# AirSenseV2_03.net
KiCad netlist of a schematic drawn in Altium Designer
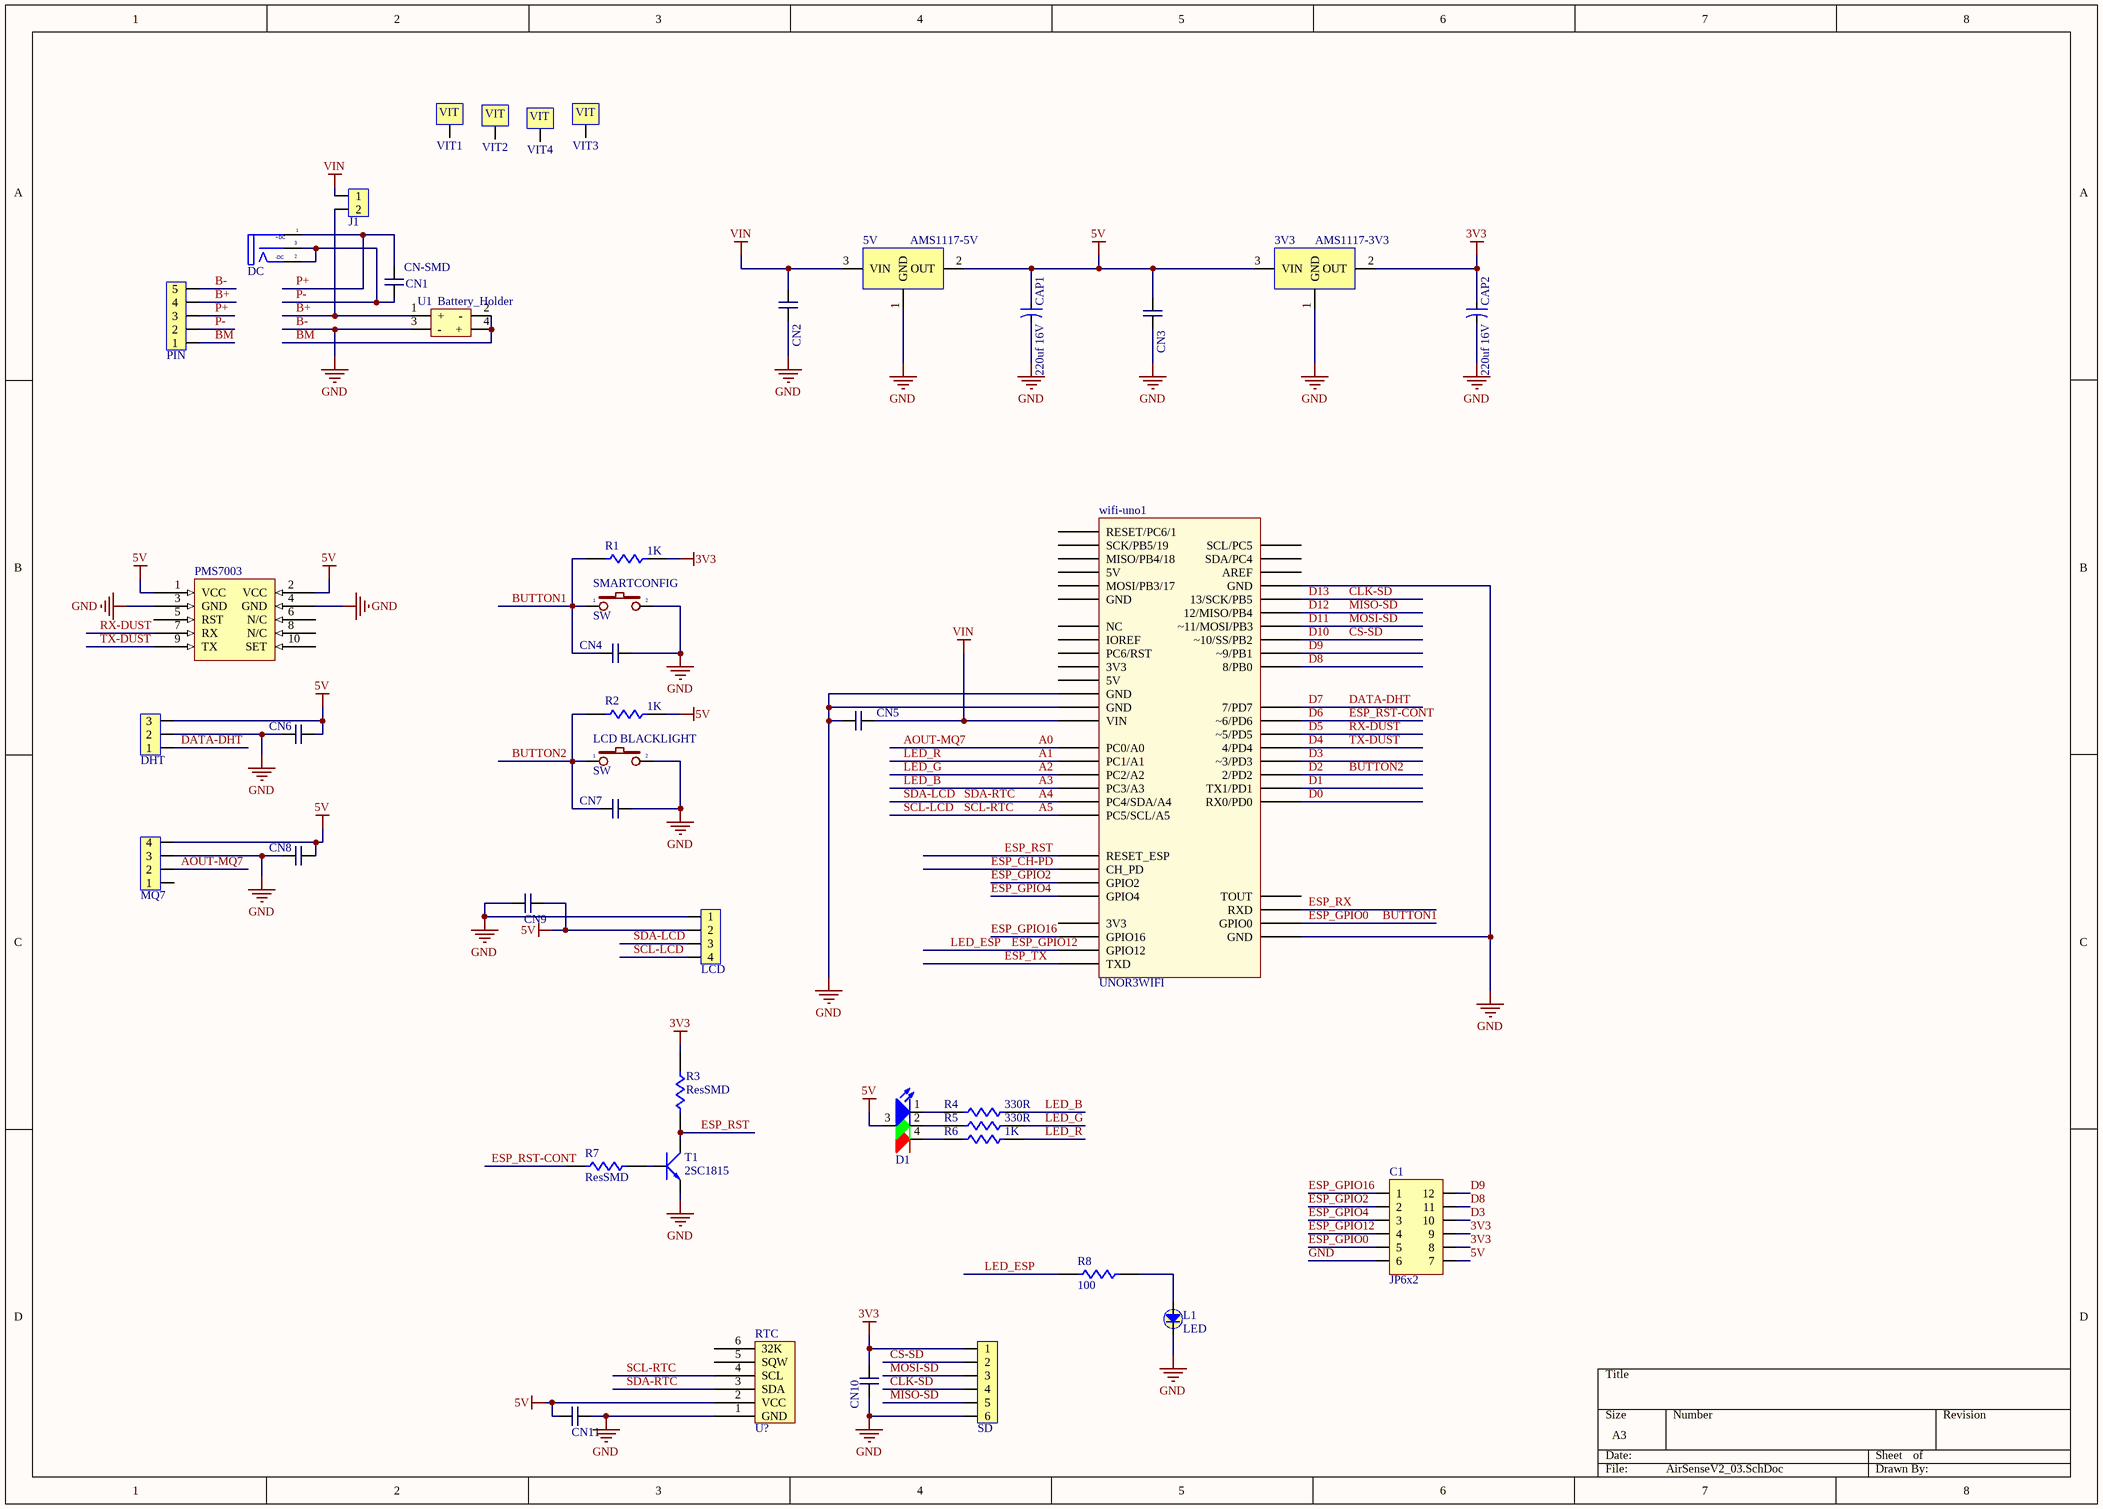
[diagram p0: AirSenseV2_03.SchDoc]

(export (version "E")
  (design (tool "Eeschema 10.0.6"))
  (components
    (comp (ref "3V3")
      (value "AMS1117-3V3")
      (footprint "SOT223")
      (description "800mA Low-Dropout Linear Regulator")
      (libsource (lib "DarkBaronLib") (part "AMS1117-3V3"))
    )
    (comp (ref "5V")
      (value "AMS1117-5V")
      (footprint "SOT223")
      (description "800mA Low-Dropout Linear Regulator")
      (libsource (lib "DarkBaronLib") (part "AMS1117-3V3"))
    )
    (comp (ref "C1")
      (value "JP6x2")
      (footprint "JP6-D2T")
      (description "WR-PHD 2.54 mm Dual Socket Header")
      (fields
        (field (name "MANUFACTURER") "Würth Elektronik eiSos GmbH")
        (field (name "PARTNO") "61301221821")
        (field (name "CREATED BY") "Karrer Zheng")
      )
      (libsource (lib "LIBRARY") (part "JP6x2"))
    )
    (comp (ref "CAP1")
      (value "220uf 16V")
      (footprint "CA-6.5x6.5")
      (description "Cap Aluminum Lytic 100uF 10V 20% (8 X 6.2mm) SMD 230mA 1000h 105C Embossed T/R")
      (libsource (lib "DarkBaronLib") (part "CAP-SMD"))
    )
    (comp (ref "CAP2")
      (value "220uf 16V")
      (footprint "CA-6.5x6.5")
      (description "Cap Aluminum Lytic 100uF 10V 20% (8 X 6.2mm) SMD 230mA 1000h 105C Embossed T/R")
      (libsource (lib "DarkBaronLib") (part "CAP-SMD"))
    )
    (comp (ref "CN1")
      (value "CN-SMD")
      (footprint "C-0805")
      (description "CAP CER 0.047UF 25V X7R 040")
      (libsource (lib "DarkBaronLib") (part "CN-SMD"))
    )
    (comp (ref "CN2")
      (value "CN-SMD")
      (footprint "C-0805")
      (description "CAP CER 0.047UF 25V X7R 040")
      (libsource (lib "DarkBaronLib") (part "CN-SMD"))
    )
    (comp (ref "CN3")
      (value "CN-SMD")
      (footprint "C-0805")
      (description "CAP CER 0.047UF 25V X7R 040")
      (libsource (lib "DarkBaronLib") (part "CN-SMD"))
    )
    (comp (ref "CN4")
      (value "CN-SMD")
      (footprint "C-0805")
      (description "CAP CER 0.047UF 25V X7R 040")
      (libsource (lib "DarkBaronLib") (part "CN-SMD"))
    )
    (comp (ref "CN5")
      (value "CN-SMD")
      (footprint "C-0805")
      (description "CAP CER 0.047UF 25V X7R 040")
      (libsource (lib "DarkBaronLib") (part "CN-SMD"))
    )
    (comp (ref "CN6")
      (value "CN-SMD")
      (footprint "C-0805")
      (description "CAP CER 0.047UF 25V X7R 040")
      (libsource (lib "DarkBaronLib") (part "CN-SMD"))
    )
    (comp (ref "CN7")
      (value "CN-SMD")
      (footprint "C-0805")
      (description "CAP CER 0.047UF 25V X7R 040")
      (libsource (lib "DarkBaronLib") (part "CN-SMD"))
    )
    (comp (ref "CN8")
      (value "CN-SMD")
      (footprint "C-0805")
      (description "CAP CER 0.047UF 25V X7R 040")
      (libsource (lib "DarkBaronLib") (part "CN-SMD"))
    )
    (comp (ref "CN9")
      (value "CN-SMD")
      (footprint "C-0805")
      (description "CAP CER 0.047UF 25V X7R 040")
      (libsource (lib "DarkBaronLib") (part "CN-SMD"))
    )
    (comp (ref "CN10")
      (value "CN-SMD")
      (footprint "C-0805")
      (description "CAP CER 0.047UF 25V X7R 040")
      (libsource (lib "DarkBaronLib") (part "CN-SMD"))
    )
    (comp (ref "CN11")
      (value "CN-SMD")
      (footprint "C-0805")
      (description "CAP CER 0.047UF 25V X7R 040")
      (libsource (lib "DarkBaronLib") (part "CN-SMD"))
    )
    (comp (ref "D1")
      (value "LED_RGB1")
      (footprint "LED RGB 5MM TYPE A")
      (libsource (lib "Tesla_Thinh") (part "LED_RGB1"))
    )
    (comp (ref "DC")
      (value "DCIN")
      (footprint "DC0")
      (description "CONN POWER JACK 2.1X5.5MM SMD")
      (libsource (lib "DarkBaronLib") (part "DCIN"))
    )
    (comp (ref "DHT")
      (value "Header3")
      (footprint "Header3")
      (description "Header IDC, 3 x 1 Pin Vertical 2.54mm Pitch (Non-Boxed, Male)")
      (libsource (lib "DarkBaronLib") (part "Header3"))
    )
    (comp (ref "J1")
      (value "JP2")
      (footprint "JP2-C1T")
      (description "WR-PHD 2.54 mm Angled Socket Header")
      (libsource (lib "DarkBaronLib") (part "JP2"))
    )
    (comp (ref "L1")
      (value "LED")
      (footprint "L-3B")
      (description "DIALIGHT         5988270107F            LED, Green, SMD, 20 mA, 2 V, 570 nm")
      (libsource (lib "DarkBaronLib") (part "LED"))
    )
    (comp (ref "LCD")
      (value "JP4")
      (footprint "JP4-C1T")
      (description "WR-PHD 2.54 mm Angled Socket Header")
      (libsource (lib "DarkBaronLib") (part "JP4"))
    )
    (comp (ref "LCD BLACKLIGHT")
      (value "SW")
      (footprint "SW1-DIP")
      (description "Switch button 2 pin")
      (libsource (lib "Tesla_Thinh") (part "SW2"))
    )
    (comp (ref "MQ7")
      (value "Header4")
      (footprint "Header4")
      (description "Header IDC, 4 x 1 Pin Vertical 2.54mm Pitch (Non-Boxed, Male)")
      (libsource (lib "DarkBaronLib") (part "Header4"))
    )
    (comp (ref "PIN")
      (value "JP5")
      (footprint "JP5-D1T")
      (description "WR-PHD 2.54 mm Angled Socket Header")
      (libsource (lib "DarkBaronLib") (part "JP5"))
    )
    (comp (ref "PMS7003")
      (value "~")
      (footprint "DUST_PMSA003")
      (libsource (lib "DarkBaronLib") (part "DUST_PMSA003"))
    )
    (comp (ref "R1")
      (value "1K")
      (footprint "R0805")
      (description "RES SMD 0.0 OHM JUMPER 1/8W 0805")
      (libsource (lib "DarkBaronLib") (part "ResSMD"))
    )
    (comp (ref "R2")
      (value "1K")
      (footprint "R0805")
      (description "RES SMD 0.0 OHM JUMPER 1/8W 0805")
      (libsource (lib "DarkBaronLib") (part "ResSMD"))
    )
    (comp (ref "R3")
      (value "ResSMD")
      (footprint "R0805")
      (description "RES SMD 0.0 OHM JUMPER 1/8W 0805")
      (libsource (lib "DarkBaronLib") (part "ResSMD"))
    )
    (comp (ref "R4")
      (value "330R")
      (footprint "R0805")
      (description "RES SMD 0.0 OHM JUMPER 1/8W 0805")
      (libsource (lib "DarkBaronLib") (part "ResSMD"))
    )
    (comp (ref "R5")
      (value "330R")
      (footprint "R0805")
      (description "RES SMD 0.0 OHM JUMPER 1/8W 0805")
      (libsource (lib "DarkBaronLib") (part "ResSMD"))
    )
    (comp (ref "R6")
      (value "1K")
      (footprint "R0805")
      (description "RES SMD 0.0 OHM JUMPER 1/8W 0805")
      (libsource (lib "DarkBaronLib") (part "ResSMD"))
    )
    (comp (ref "R7")
      (value "ResSMD")
      (footprint "R0805")
      (description "RES SMD 0.0 OHM JUMPER 1/8W 0805")
      (libsource (lib "DarkBaronLib") (part "ResSMD"))
    )
    (comp (ref "R8")
      (value "100")
      (footprint "R0805")
      (description "RES SMD 0.0 OHM JUMPER 1/8W 0805")
      (libsource (lib "DarkBaronLib") (part "ResSMD"))
    )
    (comp (ref "RTC")
      (value "U?")
      (footprint "RTC_Module")
      (libsource (lib "DarkBaronLib") (part "RTC-Module"))
    )
    (comp (ref "SD")
      (value "JP6")
      (footprint "JP6-D1T")
      (description "WR-PHD 2.54 mm Angled Socket Header")
      (libsource (lib "DarkBaronLib") (part "JP6"))
    )
    (comp (ref "SMARTCONFIG")
      (value "SW")
      (footprint "SW1-DIP")
      (description "Switch button 2 pin")
      (libsource (lib "Tesla_Thinh") (part "SW2"))
    )
    (comp (ref "T1")
      (value "2SC1815")
      (footprint "SOT23-BCE")
      (description "Bipolar Transistors - BJT NPN Epitaxial Sil")
      (libsource (lib "DarkBaronLib") (part "2SC1815"))
    )
    (comp (ref "U1")
      (value "Battery_Holder")
      (footprint "18650x2")
      (libsource (lib "DarkBaronLib") (part "Battery_Holder"))
    )
    (comp (ref "VIT1")
      (value "VIT")
      (footprint "VIT")
      (description "Oc Vit")
      (libsource (lib "DarkBaronLib") (part "VIT"))
    )
    (comp (ref "VIT2")
      (value "VIT")
      (footprint "VIT")
      (description "Oc Vit")
      (libsource (lib "DarkBaronLib") (part "VIT"))
    )
    (comp (ref "VIT3")
      (value "VIT")
      (footprint "VIT")
      (description "Oc Vit")
      (libsource (lib "DarkBaronLib") (part "VIT"))
    )
    (comp (ref "VIT4")
      (value "VIT")
      (footprint "VIT")
      (description "Oc Vit")
      (libsource (lib "DarkBaronLib") (part "VIT"))
    )
    (comp (ref "wifi-uno1")
      (value "UNOR3WIFI")
      (footprint "UNOR3WIFI")
      (libsource (lib "AirSenseV2_03") (part "UNOR3WIFI"))
    )
  )
  (nets
    (net (code "1") (name "/A0") (class "Default")
      (node (ref "MQ7") (pin "2") (pinfunction "2_2") (pintype "passive"))
      (node (ref "wifi-uno1") (pin "PC0") (pinfunction "PC0/A0_PC0") (pintype "passive"))
    )
    (net (code "2") (name "/A1") (class "Default")
      (node (ref "R6") (pin "1") (pinfunction "1_1") (pintype "passive"))
      (node (ref "wifi-uno1") (pin "PC1") (pinfunction "PC1/A1_PC1") (pintype "passive"))
    )
    (net (code "3") (name "/A2") (class "Default")
      (node (ref "R5") (pin "1") (pinfunction "1_1") (pintype "passive"))
      (node (ref "wifi-uno1") (pin "PC2") (pinfunction "PC2/A2_PC2") (pintype "passive"))
    )
    (net (code "4") (name "/A3") (class "Default")
      (node (ref "R4") (pin "1") (pinfunction "1_1") (pintype "passive"))
      (node (ref "wifi-uno1") (pin "PC3") (pinfunction "PC3/A3_PC3") (pintype "passive"))
    )
    (net (code "5") (name "/A4") (class "Default")
      (node (ref "LCD") (pin "3") (pinfunction "3_3") (pintype "passive"))
      (node (ref "RTC") (pin "3") (pinfunction "SDA_3") (pintype "passive"))
      (node (ref "wifi-uno1") (pin "PC4") (pinfunction "PC4/SDA/A4_PC4") (pintype "passive"))
    )
    (net (code "6") (name "/A5") (class "Default")
      (node (ref "LCD") (pin "4") (pinfunction "4_4") (pintype "passive"))
      (node (ref "RTC") (pin "4") (pinfunction "SCL_4") (pintype "passive"))
      (node (ref "wifi-uno1") (pin "PC5") (pinfunction "PC5/SCL/A5_PC5") (pintype "passive"))
    )
    (net (code "7") (name "/B+") (class "Default")
      (node (ref "J1") (pin "2") (pinfunction "2_2") (pintype "passive"))
      (node (ref "PIN") (pin "4") (pinfunction "4_4") (pintype "passive"))
      (node (ref "U1") (pin "1") (pinfunction "+_1") (pintype "power_in"))
    )
    (net (code "8") (name "/BM") (class "Default")
      (node (ref "PIN") (pin "1") (pinfunction "1_1") (pintype "passive"))
      (node (ref "U1") (pin "2") (pinfunction "-_2") (pintype "power_in"))
      (node (ref "U1") (pin "4") (pinfunction "+_4") (pintype "power_in"))
    )
    (net (code "9") (name "/BUTTON1") (class "Default")
      (node (ref "C1") (pin "5") (pinfunction "5_5") (pintype "passive"))
      (node (ref "CN4") (pin "1") (pinfunction "1_1") (pintype "passive"))
      (node (ref "R1") (pin "2") (pinfunction "2_2") (pintype "passive"))
      (node (ref "SMARTCONFIG") (pin "1") (pinfunction "1_1") (pintype "passive"))
      (node (ref "wifi-uno1") (pin "GPIO0") (pinfunction "GPIO0_GPIO0") (pintype "passive"))
    )
    (net (code "10") (name "/BUTTON2") (class "Default")
      (node (ref "CN7") (pin "1") (pinfunction "1_1") (pintype "passive"))
      (node (ref "LCD BLACKLIGHT") (pin "1") (pinfunction "1_1") (pintype "passive"))
      (node (ref "R2") (pin "2") (pinfunction "2_2") (pintype "passive"))
      (node (ref "wifi-uno1") (pin "PD2") (pinfunction "2/PD2_PD2") (pintype "passive"))
    )
    (net (code "11") (name "/CLK-SD") (class "Default")
      (node (ref "SD") (pin "4") (pinfunction "4_4") (pintype "passive"))
      (node (ref "wifi-uno1") (pin "PB5") (pinfunction "13/SCK/PB5_PB5") (pintype "passive"))
    )
    (net (code "12") (name "/CS-SD") (class "Default")
      (node (ref "SD") (pin "2") (pinfunction "2_2") (pintype "passive"))
      (node (ref "wifi-uno1") (pin "PB2") (pinfunction "~10/SS/PB2_PB2") (pintype "passive"))
    )
    (net (code "13") (name "/D0") (class "Default")
      (node (ref "wifi-uno1") (pin "PD0") (pinfunction "RX0/PD0_PD0") (pintype "passive"))
    )
    (net (code "14") (name "/D1") (class "Default")
      (node (ref "wifi-uno1") (pin "PD1") (pinfunction "TX1/PD1_PD1") (pintype "passive"))
    )
    (net (code "15") (name "/D3") (class "Default")
      (node (ref "C1") (pin "10") (pinfunction "10_10") (pintype "passive"))
      (node (ref "wifi-uno1") (pin "PD3") (pinfunction "~3/PD3_PD3") (pintype "passive"))
    )
    (net (code "16") (name "/D4") (class "Default")
      (node (ref "PMS7003") (pin "9") (pinfunction "TX_9") (pintype "input"))
      (node (ref "wifi-uno1") (pin "PD4") (pinfunction "4/PD4_PD4") (pintype "passive"))
    )
    (net (code "17") (name "/D5") (class "Default")
      (node (ref "PMS7003") (pin "7") (pinfunction "RX_7") (pintype "input"))
      (node (ref "wifi-uno1") (pin "PD5") (pinfunction "~5/PD5_PD5") (pintype "passive"))
    )
    (net (code "18") (name "/D6") (class "Default")
      (node (ref "R7") (pin "2") (pinfunction "2_2") (pintype "passive"))
      (node (ref "wifi-uno1") (pin "PD6") (pinfunction "~6/PD6_PD6") (pintype "passive"))
    )
    (net (code "19") (name "/D7") (class "Default")
      (node (ref "DHT") (pin "1") (pinfunction "1_1") (pintype "passive"))
      (node (ref "wifi-uno1") (pin "PD7") (pinfunction "7/PD7_PD7") (pintype "passive"))
    )
    (net (code "20") (name "/D8") (class "Default")
      (node (ref "C1") (pin "11") (pinfunction "11_11") (pintype "passive"))
      (node (ref "wifi-uno1") (pin "PB0") (pinfunction "8/PB0_PB0") (pintype "passive"))
    )
    (net (code "21") (name "/D9") (class "Default")
      (node (ref "C1") (pin "12") (pinfunction "12_12") (pintype "passive"))
      (node (ref "wifi-uno1") (pin "PB1") (pinfunction "~9/PB1_PB1") (pintype "passive"))
    )
    (net (code "22") (name "/D11") (class "Default")
      (node (ref "SD") (pin "3") (pinfunction "3_3") (pintype "passive"))
      (node (ref "wifi-uno1") (pin "PB3") (pinfunction "~11/MOSI/PB3_PB3") (pintype "passive"))
    )
    (net (code "23") (name "/D12") (class "Default")
      (node (ref "SD") (pin "5") (pinfunction "5_5") (pintype "passive"))
      (node (ref "wifi-uno1") (pin "PB4") (pinfunction "12/MISO/PB4_PB4") (pintype "passive"))
    )
    (net (code "24") (name "/ESP_CH-PD") (class "Default")
      (node (ref "wifi-uno1") (pin "CH_PD") (pinfunction "CH_PD_CH_PD") (pintype "passive"))
    )
    (net (code "25") (name "/ESP_GPIO2") (class "Default")
      (node (ref "C1") (pin "2") (pinfunction "2_2") (pintype "passive"))
      (node (ref "wifi-uno1") (pin "GPIO2") (pinfunction "GPIO2_GPIO2") (pintype "passive"))
    )
    (net (code "26") (name "/ESP_GPIO4") (class "Default")
      (node (ref "C1") (pin "3") (pinfunction "3_3") (pintype "passive"))
      (node (ref "wifi-uno1") (pin "GPIO4") (pinfunction "GPIO4_GPIO4") (pintype "passive"))
    )
    (net (code "27") (name "/ESP_GPIO12") (class "Default")
      (node (ref "C1") (pin "4") (pinfunction "4_4") (pintype "passive"))
      (node (ref "R8") (pin "1") (pinfunction "1_1") (pintype "passive"))
      (node (ref "wifi-uno1") (pin "GPIO12") (pinfunction "GPIO12_GPIO12") (pintype "passive"))
    )
    (net (code "28") (name "/ESP_GPIO16") (class "Default")
      (node (ref "C1") (pin "1") (pinfunction "1_1") (pintype "passive"))
      (node (ref "wifi-uno1") (pin "GPIO16") (pinfunction "GPIO16_GPIO16") (pintype "passive"))
    )
    (net (code "29") (name "/ESP_RST") (class "Default")
      (node (ref "R3") (pin "2") (pinfunction "2_2") (pintype "passive"))
      (node (ref "T1") (pin "2") (pinfunction "C_2") (pintype "passive"))
      (node (ref "wifi-uno1") (pin "RESET_ESP") (pinfunction "RESET_ESP_RESET_ESP") (pintype "passive"))
    )
    (net (code "30") (name "/ESP_RX") (class "Default")
      (node (ref "wifi-uno1") (pin "RXD") (pinfunction "RXD_RXD") (pintype "passive"))
    )
    (net (code "31") (name "/ESP_TX") (class "Default")
      (node (ref "wifi-uno1") (pin "TXD") (pinfunction "TXD_TXD") (pintype "passive"))
    )
    (net (code "32") (name "/P+") (class "Default")
      (node (ref "CN1") (pin "2") (pinfunction "2_2") (pintype "passive"))
      (node (ref "DC") (pin "1") (pinfunction "T_1") (pintype "passive"))
      (node (ref "PIN") (pin "3") (pinfunction "3_3") (pintype "passive"))
    )
    (net (code "33") (name "/P-") (class "Default")
      (node (ref "CN1") (pin "1") (pinfunction "1_1") (pintype "passive"))
      (node (ref "DC") (pin "2") (pinfunction "TN_2") (pintype "passive"))
      (node (ref "DC") (pin "3") (pinfunction "S_3") (pintype "power_in"))
      (node (ref "PIN") (pin "2") (pinfunction "2_2") (pintype "passive"))
    )
    (net (code "34") (name "3V3") (class "Default")
      (node (ref "3V3") (pin "2") (pinfunction "OUT_2") (pintype "passive"))
      (node (ref "C1") (pin "8") (pinfunction "8_8") (pintype "passive"))
      (node (ref "C1") (pin "9") (pinfunction "9_9") (pintype "passive"))
      (node (ref "CAP2") (pin "1") (pinfunction "1_1") (pintype "passive"))
      (node (ref "CN10") (pin "2") (pinfunction "2_2") (pintype "passive"))
      (node (ref "R1") (pin "1") (pinfunction "1_1") (pintype "passive"))
      (node (ref "R3") (pin "1") (pinfunction "1_1") (pintype "passive"))
      (node (ref "SD") (pin "1") (pinfunction "1_1") (pintype "passive"))
    )
    (net (code "35") (name "5V") (class "Default")
      (node (ref "3V3") (pin "3") (pinfunction "VIN_3") (pintype "passive"))
      (node (ref "5V") (pin "2") (pinfunction "OUT_2") (pintype "passive"))
      (node (ref "C1") (pin "7") (pinfunction "7_7") (pintype "passive"))
      (node (ref "CAP1") (pin "1") (pinfunction "1_1") (pintype "passive"))
      (node (ref "CN11") (pin "1") (pinfunction "1_1") (pintype "passive"))
      (node (ref "CN3") (pin "2") (pinfunction "2_2") (pintype "passive"))
      (node (ref "CN6") (pin "2") (pinfunction "2_2") (pintype "passive"))
      (node (ref "CN8") (pin "2") (pinfunction "2_2") (pintype "passive"))
      (node (ref "CN9") (pin "2") (pinfunction "2_2") (pintype "passive"))
      (node (ref "D1") (pin "3") (pinfunction "A_3") (pintype "passive"))
      (node (ref "DHT") (pin "3") (pinfunction "3_3") (pintype "passive"))
      (node (ref "LCD") (pin "2") (pinfunction "2_2") (pintype "passive"))
      (node (ref "MQ7") (pin "4") (pinfunction "4_4") (pintype "passive"))
      (node (ref "PMS7003") (pin "1") (pinfunction "VCC_1") (pintype "input"))
      (node (ref "PMS7003") (pin "2") (pinfunction "VCC_2") (pintype "input"))
      (node (ref "R2") (pin "1") (pinfunction "1_1") (pintype "passive"))
      (node (ref "RTC") (pin "2") (pinfunction "VCC_2") (pintype "passive"))
    )
    (net (code "36") (name "GND") (class "Default")
      (node (ref "3V3") (pin "1") (pinfunction "GND_1") (pintype "passive"))
      (node (ref "5V") (pin "1") (pinfunction "GND_1") (pintype "passive"))
      (node (ref "C1") (pin "6") (pinfunction "6_6") (pintype "passive"))
      (node (ref "CAP1") (pin "2") (pinfunction "2_2") (pintype "passive"))
      (node (ref "CAP2") (pin "2") (pinfunction "2_2") (pintype "passive"))
      (node (ref "CN10") (pin "1") (pinfunction "1_1") (pintype "passive"))
      (node (ref "CN11") (pin "2") (pinfunction "2_2") (pintype "passive"))
      (node (ref "CN2") (pin "1") (pinfunction "1_1") (pintype "passive"))
      (node (ref "CN3") (pin "1") (pinfunction "1_1") (pintype "passive"))
      (node (ref "CN4") (pin "2") (pinfunction "2_2") (pintype "passive"))
      (node (ref "CN5") (pin "1") (pinfunction "1_1") (pintype "passive"))
      (node (ref "CN6") (pin "1") (pinfunction "1_1") (pintype "passive"))
      (node (ref "CN7") (pin "2") (pinfunction "2_2") (pintype "passive"))
      (node (ref "CN8") (pin "1") (pinfunction "1_1") (pintype "passive"))
      (node (ref "CN9") (pin "1") (pinfunction "1_1") (pintype "passive"))
      (node (ref "DHT") (pin "2") (pinfunction "2_2") (pintype "passive"))
      (node (ref "L1") (pin "2") (pinfunction "K_2") (pintype "passive"))
      (node (ref "LCD") (pin "1") (pinfunction "1_1") (pintype "passive"))
      (node (ref "LCD BLACKLIGHT") (pin "2") (pinfunction "2_2") (pintype "passive"))
      (node (ref "MQ7") (pin "3") (pinfunction "3_3") (pintype "passive"))
      (node (ref "PIN") (pin "5") (pinfunction "5_5") (pintype "passive"))
      (node (ref "PMS7003") (pin "3") (pinfunction "GND_3") (pintype "input"))
      (node (ref "PMS7003") (pin "4") (pinfunction "GND_4") (pintype "input"))
      (node (ref "RTC") (pin "1") (pinfunction "GND_1") (pintype "passive"))
      (node (ref "SD") (pin "6") (pinfunction "6_6") (pintype "passive"))
      (node (ref "SMARTCONFIG") (pin "2") (pinfunction "2_2") (pintype "passive"))
      (node (ref "T1") (pin "3") (pinfunction "E_3") (pintype "passive"))
      (node (ref "U1") (pin "3") (pinfunction "-_3") (pintype "power_in"))
      (node (ref "wifi-uno1") (pin "GND") (pinfunction "GND_GND") (pintype "power_in"))
    )
    (net (code "37") (name "Net-(D1-K_B)") (class "Default")
      (node (ref "D1") (pin "1") (pinfunction "K_B_1") (pintype "passive"))
      (node (ref "R4") (pin "2") (pinfunction "2_2") (pintype "passive"))
    )
    (net (code "38") (name "Net-(D1-K_G)") (class "Default")
      (node (ref "D1") (pin "2") (pinfunction "K_G_2") (pintype "passive"))
      (node (ref "R5") (pin "2") (pinfunction "2_2") (pintype "passive"))
    )
    (net (code "39") (name "Net-(D1-K_R)") (class "Default")
      (node (ref "D1") (pin "4") (pinfunction "K_R_4") (pintype "passive"))
      (node (ref "R6") (pin "2") (pinfunction "2_2") (pintype "passive"))
    )
    (net (code "40") (name "Net-(L1-A)") (class "Default")
      (node (ref "L1") (pin "1") (pinfunction "A_1") (pintype "passive"))
      (node (ref "R8") (pin "2") (pinfunction "2_2") (pintype "passive"))
    )
    (net (code "41") (name "Net-(T1-B)") (class "Default")
      (node (ref "R7") (pin "1") (pinfunction "1_1") (pintype "passive"))
      (node (ref "T1") (pin "1") (pinfunction "B_1") (pintype "passive"))
    )
    (net (code "42") (name "VIN") (class "Default")
      (node (ref "5V") (pin "3") (pinfunction "VIN_3") (pintype "passive"))
      (node (ref "CN2") (pin "2") (pinfunction "2_2") (pintype "passive"))
      (node (ref "CN5") (pin "2") (pinfunction "2_2") (pintype "passive"))
      (node (ref "J1") (pin "1") (pinfunction "1_1") (pintype "passive"))
      (node (ref "wifi-uno1") (pin "VIN") (pinfunction "VIN_VIN") (pintype "power_in"))
    )
    (net (code "43") (name "unconnected-(MQ7-Pad1)") (class "Default")
      (node (ref "MQ7") (pin "1") (pinfunction "1_1") (pintype "passive"))
    )
    (net (code "44") (name "unconnected-(PMS7003-N{slash}C-Pad6)") (class "Default")
      (node (ref "PMS7003") (pin "6") (pinfunction "N/C_6") (pintype "input"))
    )
    (net (code "45") (name "unconnected-(PMS7003-N{slash}C-Pad8)") (class "Default")
      (node (ref "PMS7003") (pin "8") (pinfunction "N/C_8") (pintype "input"))
    )
    (net (code "46") (name "unconnected-(PMS7003-RST-Pad5)") (class "Default")
      (node (ref "PMS7003") (pin "5") (pinfunction "RST_5") (pintype "input"))
    )
    (net (code "47") (name "unconnected-(PMS7003-SET-Pad10)") (class "Default")
      (node (ref "PMS7003") (pin "10") (pinfunction "SET_10") (pintype "input"))
    )
    (net (code "48") (name "unconnected-(RTC-32K-Pad6)") (class "Default")
      (node (ref "RTC") (pin "6") (pinfunction "32K_6") (pintype "passive"))
    )
    (net (code "49") (name "unconnected-(RTC-SQW-Pad5)") (class "Default")
      (node (ref "RTC") (pin "5") (pinfunction "SQW_5") (pintype "passive"))
    )
    (net (code "50") (name "unconnected-(VIT1-1-PadVIT1)") (class "Default")
      (node (ref "VIT1") (pin "VIT1") (pinfunction "1_VIT1") (pintype "passive"))
    )
    (net (code "51") (name "unconnected-(VIT2-1-PadVIT1)") (class "Default")
      (node (ref "VIT2") (pin "VIT1") (pinfunction "1_VIT1") (pintype "passive"))
    )
    (net (code "52") (name "unconnected-(VIT3-1-PadVIT1)") (class "Default")
      (node (ref "VIT3") (pin "VIT1") (pinfunction "1_VIT1") (pintype "passive"))
    )
    (net (code "53") (name "unconnected-(VIT4-1-PadVIT1)") (class "Default")
      (node (ref "VIT4") (pin "VIT1") (pinfunction "1_VIT1") (pintype "passive"))
    )
    (net (code "54") (name "unconnected-(wifi-uno1-MISO{slash}PB4{slash}18-PadPB4)") (class "Default")
      (node (ref "wifi-uno1") (pin "PB4") (pinfunction "MISO/PB4/18_PB4") (pintype "passive"))
    )
    (net (code "55") (name "unconnected-(wifi-uno1-MOSI{slash}PB3{slash}17-PadPB3)") (class "Default")
      (node (ref "wifi-uno1") (pin "PB3") (pinfunction "MOSI/PB3/17_PB3") (pintype "passive"))
    )
    (net (code "56") (name "unconnected-(wifi-uno1-PC6{slash}RST-PadPC6)") (class "Default")
      (node (ref "wifi-uno1") (pin "PC6") (pinfunction "PC6/RST_PC6") (pintype "passive"))
    )
    (net (code "57") (name "unconnected-(wifi-uno1-Pad3V3)") (class "Default")
      (node (ref "wifi-uno1") (pin "3V3") (pinfunction "3V3_3V3") (pintype "power_in"))
    )
    (net (code "58") (name "unconnected-(wifi-uno1-Pad3V3)_1") (class "Default")
      (node (ref "wifi-uno1") (pin "3V3") (pinfunction "3V3_3V3") (pintype "power_in"))
    )
    (net (code "59") (name "unconnected-(wifi-uno1-Pad5V)") (class "Default")
      (node (ref "wifi-uno1") (pin "5V") (pinfunction "5V_5V") (pintype "power_in"))
    )
    (net (code "60") (name "unconnected-(wifi-uno1-Pad5V)_1") (class "Default")
      (node (ref "wifi-uno1") (pin "5V") (pinfunction "5V_5V") (pintype "power_in"))
    )
    (net (code "61") (name "unconnected-(wifi-uno1-PadAREF)") (class "Default")
      (node (ref "wifi-uno1") (pin "AREF") (pinfunction "AREF_AREF") (pintype "passive"))
    )
    (net (code "62") (name "unconnected-(wifi-uno1-PadGND)") (class "Default")
      (node (ref "wifi-uno1") (pin "GND") (pinfunction "GND_GND") (pintype "power_in"))
    )
    (net (code "63") (name "unconnected-(wifi-uno1-PadIOREF)") (class "Default")
      (node (ref "wifi-uno1") (pin "IOREF") (pinfunction "IOREF_IOREF") (pintype "passive"))
    )
    (net (code "64") (name "unconnected-(wifi-uno1-PadNC)") (class "Default")
      (node (ref "wifi-uno1") (pin "NC") (pinfunction "NC_NC") (pintype "passive"))
    )
    (net (code "65") (name "unconnected-(wifi-uno1-PadTOUT)") (class "Default")
      (node (ref "wifi-uno1") (pin "TOUT") (pinfunction "TOUT_TOUT") (pintype "passive"))
    )
    (net (code "66") (name "unconnected-(wifi-uno1-RESET{slash}PC6{slash}1-PadPC6)") (class "Default")
      (node (ref "wifi-uno1") (pin "PC6") (pinfunction "RESET/PC6/1_PC6") (pintype "passive"))
    )
    (net (code "67") (name "unconnected-(wifi-uno1-SCK{slash}PB5{slash}19-PadPB5)") (class "Default")
      (node (ref "wifi-uno1") (pin "PB5") (pinfunction "SCK/PB5/19_PB5") (pintype "passive"))
    )
    (net (code "68") (name "unconnected-(wifi-uno1-SCL{slash}PC5-PadPC5)") (class "Default")
      (node (ref "wifi-uno1") (pin "PC5") (pinfunction "SCL/PC5_PC5") (pintype "passive"))
    )
    (net (code "69") (name "unconnected-(wifi-uno1-SDA{slash}PC4-PadPC4)") (class "Default")
      (node (ref "wifi-uno1") (pin "PC4") (pinfunction "SDA/PC4_PC4") (pintype "passive"))
    )
  )
)
